# Spectra1.net
KiCad netlist of a schematic drawn in EAGLE
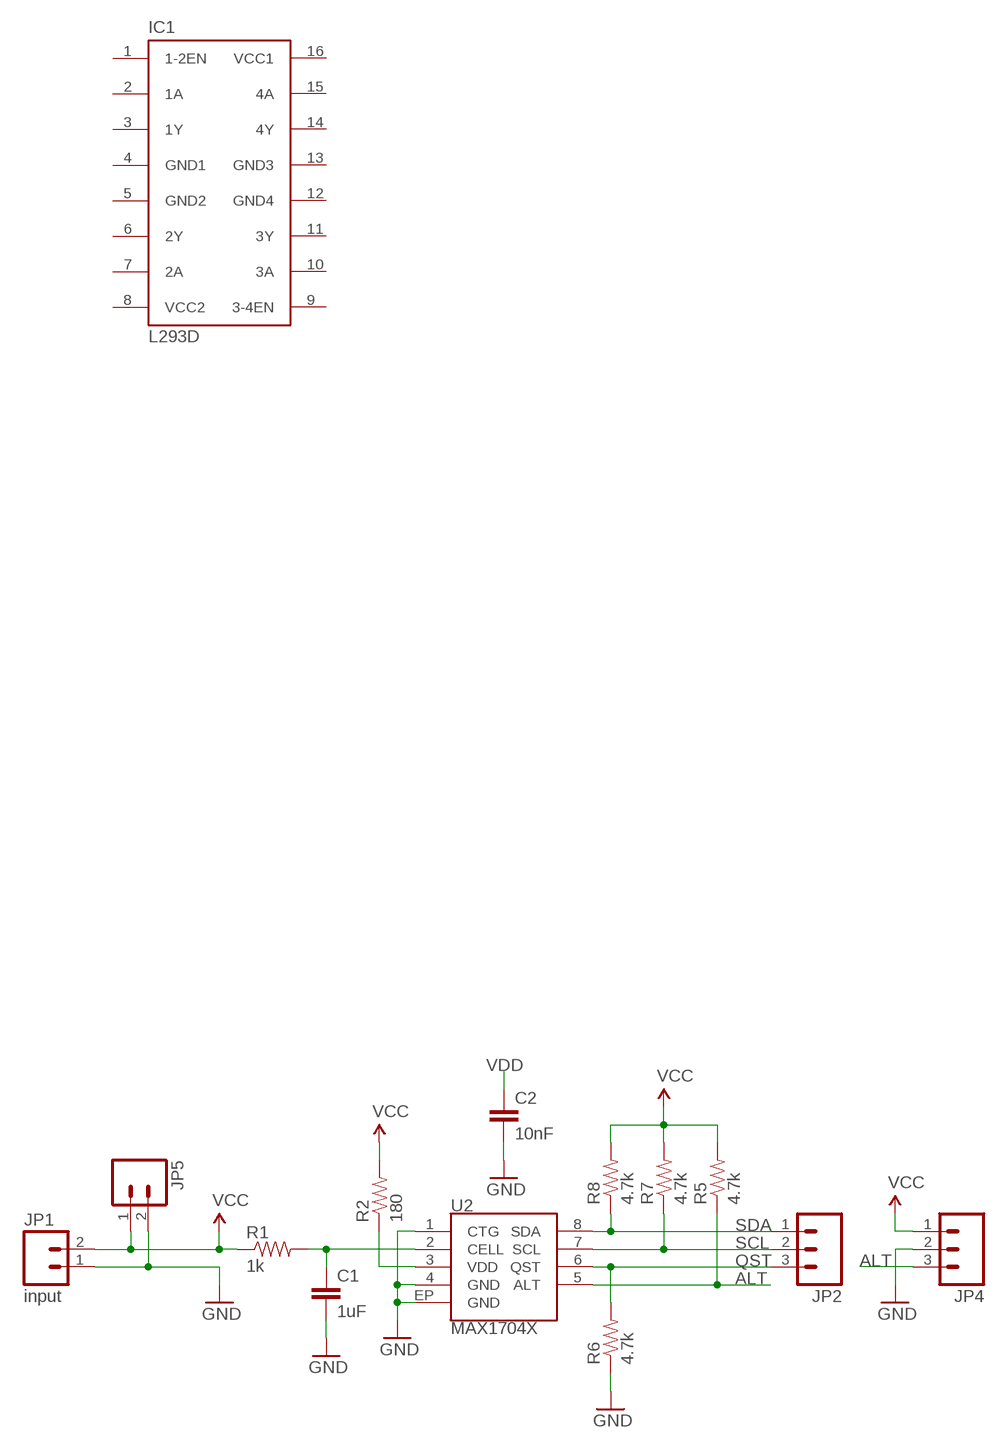
[diagram p0: schematic, sheet 1, part 1 of 2]
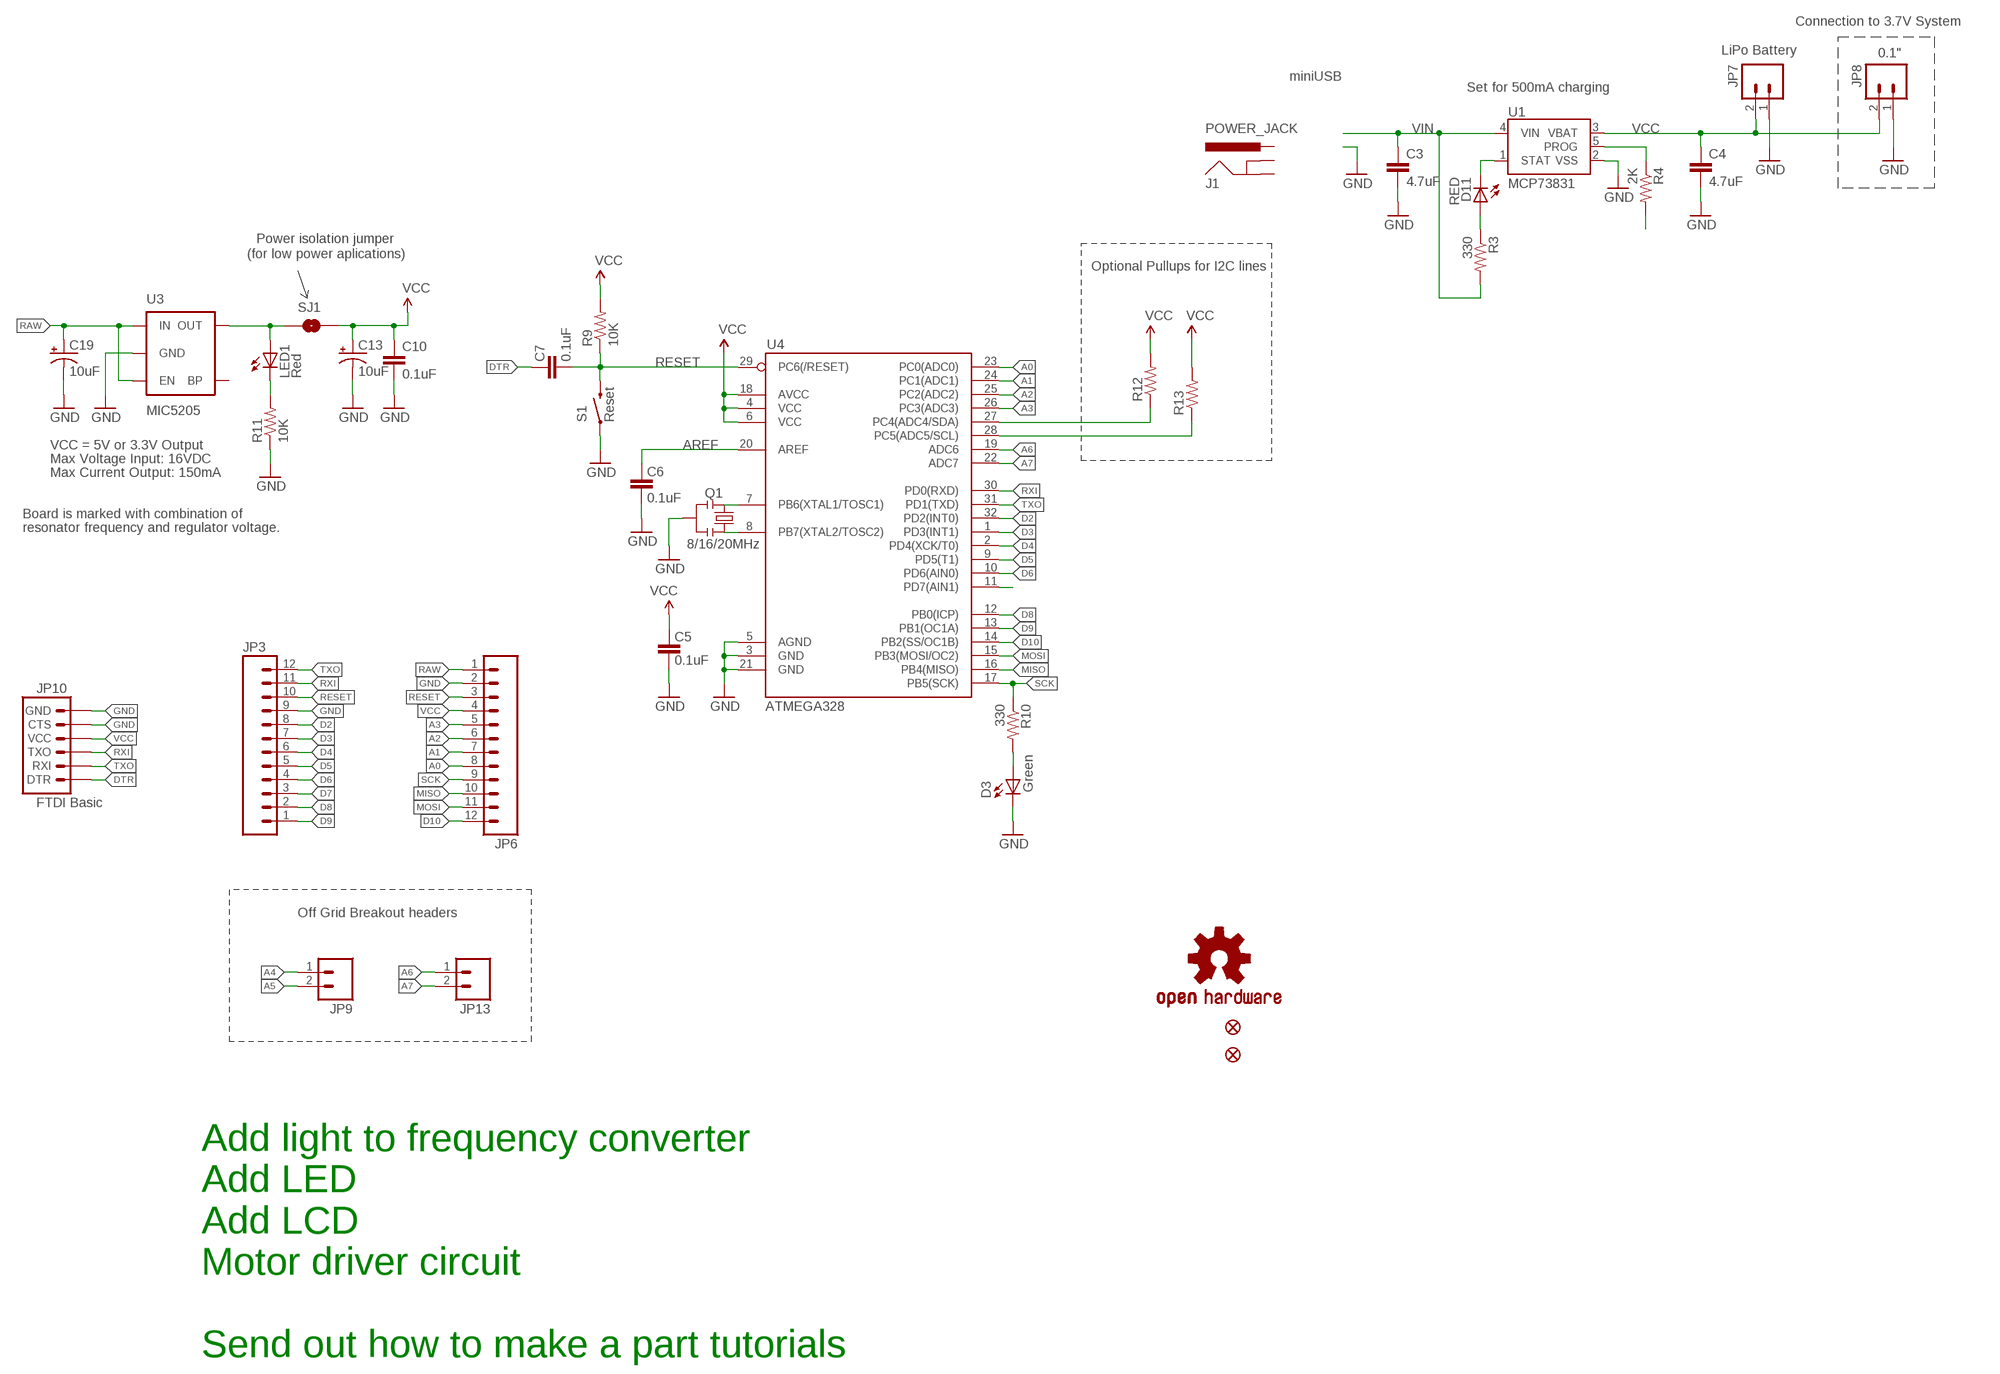
[diagram p1: schematic, sheet 1, part 2 of 2]

(export (version "E")
  (design (tool "Eeschema 10.0.6"))
  (components
    (comp (ref "C1")
      (value "1uF")
      (footprint "eagle-import:0402-CAP")
      (libsource (lib "eagle-import") (part "CAP0402-CAP"))
    )
    (comp (ref "C2")
      (value "10nF")
      (footprint "eagle-import:0402-CAP")
      (libsource (lib "eagle-import") (part "CAP0402-CAP"))
    )
    (comp (ref "C3")
      (value "4.7uF")
      (footprint "eagle-import:0402-CAP")
      (libsource (lib "eagle-import") (part "CAP0402-CAP"))
    )
    (comp (ref "C4")
      (value "4.7uF")
      (footprint "eagle-import:0402-CAP")
      (libsource (lib "eagle-import") (part "CAP0402-CAP"))
    )
    (comp (ref "C5")
      (value "0.1uF")
      (footprint "eagle-import:0603-CAP")
      (libsource (lib "eagle-import") (part "CAP0603-CAP"))
    )
    (comp (ref "C6")
      (value "0.1uF")
      (footprint "eagle-import:0603-CAP")
      (libsource (lib "eagle-import") (part "CAP0603-CAP"))
    )
    (comp (ref "C7")
      (value "0.1uF")
      (footprint "eagle-import:0603-CAP")
      (libsource (lib "eagle-import") (part "CAP0603-CAP"))
    )
    (comp (ref "C10")
      (value "0.1uF")
      (footprint "eagle-import:0603-CAP")
      (libsource (lib "eagle-import") (part "CAP0603-CAP"))
    )
    (comp (ref "C13")
      (value "10uF")
      (footprint "eagle-import:EIA3216")
      (libsource (lib "eagle-import") (part "CAP_POL1206"))
    )
    (comp (ref "C19")
      (value "10uF")
      (footprint "eagle-import:EIA3216")
      (libsource (lib "eagle-import") (part "CAP_POL1206"))
    )
    (comp (ref "D3")
      (value "Green")
      (footprint "eagle-import:0603-LED-ALT1")
      (libsource (lib "eagle-import") (part "LED"))
    )
    (comp (ref "D11")
      (value "RED")
      (footprint "eagle-import:LED-0603")
      (libsource (lib "eagle-import") (part "LED0603"))
    )
    (comp (ref "IC1")
      (value "L293D")
      (footprint "eagle-import:DIL16")
      (libsource (lib "eagle-import") (part "L293D"))
    )
    (comp (ref "J1")
      (value "POWER_JACK")
      (footprint "eagle-import:POWER_JACK_PTH")
      (libsource (lib "eagle-import") (part "POWER_JACK"))
    )
    (comp (ref "JP1")
      (value "input")
      (footprint "eagle-import:JST-2-SMD")
      (libsource (lib "eagle-import") (part "M02-JST-2MM-SMT"))
    )
    (comp (ref "JP2")
      (value "M03PTH")
      (footprint "eagle-import:1X03")
      (libsource (lib "eagle-import") (part "M03PTH"))
    )
    (comp (ref "JP3")
      (value "M12PTH")
      (footprint "eagle-import:1X12")
      (libsource (lib "eagle-import") (part "M12PTH"))
    )
    (comp (ref "JP4")
      (value "M03PTH")
      (footprint "eagle-import:1X03")
      (libsource (lib "eagle-import") (part "M03PTH"))
    )
    (comp (ref "JP5")
      (value "M02PTH")
      (footprint "eagle-import:1X02")
      (libsource (lib "eagle-import") (part "M02PTH"))
    )
    (comp (ref "JP6")
      (value "M12PTH")
      (footprint "eagle-import:1X12")
      (libsource (lib "eagle-import") (part "M12PTH"))
    )
    (comp (ref "JP7")
      (value "LiPo Battery")
      (footprint "eagle-import:JST-2-SMD")
      (libsource (lib "eagle-import") (part "M02-JST-2MM-SMT"))
    )
    (comp (ref "JP8")
      (value "M02PTH")
      (footprint "eagle-import:1X02")
      (libsource (lib "eagle-import") (part "M02PTH"))
    )
    (comp (ref "JP9")
      (value "M02PTH")
      (footprint "eagle-import:1X02")
      (libsource (lib "eagle-import") (part "M02PTH"))
    )
    (comp (ref "JP10")
      (value "FTDI Basic")
      (footprint "eagle-import:1X06")
      (libsource (lib "eagle-import") (part "ARDUINO_SERIAL_PROGRAMPTH"))
    )
    (comp (ref "JP11")
      (value "FIDUCIALUFIDUCIAL")
      (footprint "eagle-import:MICRO-FIDUCIAL")
      (libsource (lib "eagle-import") (part "FIDUCIALUFIDUCIAL"))
    )
    (comp (ref "JP12")
      (value "FIDUCIALUFIDUCIAL")
      (footprint "eagle-import:MICRO-FIDUCIAL")
      (libsource (lib "eagle-import") (part "FIDUCIALUFIDUCIAL"))
    )
    (comp (ref "JP13")
      (value "M02PTH")
      (footprint "eagle-import:1X02")
      (libsource (lib "eagle-import") (part "M02PTH"))
    )
    (comp (ref "LED1")
      (value "Red")
      (footprint "eagle-import:0603-LED-ALT1")
      (libsource (lib "eagle-import") (part "LED"))
    )
    (comp (ref "Q1")
      (value "8/16/20MHz")
      (footprint "eagle-import:RESONATOR-SMD-1_1")
      (libsource (lib "eagle-import") (part "RESONATOR1{colon}1"))
    )
    (comp (ref "R1")
      (value "1k")
      (footprint "eagle-import:0402-RES")
      (libsource (lib "eagle-import") (part "RESISTOR0402-RES"))
    )
    (comp (ref "R2")
      (value "180")
      (footprint "eagle-import:0402-RES")
      (libsource (lib "eagle-import") (part "RESISTOR0402-RES"))
    )
    (comp (ref "R3")
      (value "330")
      (footprint "eagle-import:0402-RES")
      (libsource (lib "eagle-import") (part "RESISTOR0402-RES"))
    )
    (comp (ref "R4")
      (value "2K")
      (footprint "eagle-import:0402-RES")
      (libsource (lib "eagle-import") (part "RESISTOR0402-RES"))
    )
    (comp (ref "R5")
      (value "4.7k")
      (footprint "eagle-import:0402-RES")
      (libsource (lib "eagle-import") (part "RESISTOR0402-RES"))
    )
    (comp (ref "R6")
      (value "4.7k")
      (footprint "eagle-import:0402-RES")
      (libsource (lib "eagle-import") (part "RESISTOR0402-RES"))
    )
    (comp (ref "R7")
      (value "4.7k")
      (footprint "eagle-import:0402-RES")
      (libsource (lib "eagle-import") (part "RESISTOR0402-RES"))
    )
    (comp (ref "R8")
      (value "4.7k")
      (footprint "eagle-import:0402-RES")
      (libsource (lib "eagle-import") (part "RESISTOR0402-RES"))
    )
    (comp (ref "R9")
      (value "10K")
      (footprint "eagle-import:0603-RES")
      (libsource (lib "eagle-import") (part "RESISTOR0603-RES"))
    )
    (comp (ref "R10")
      (value "330")
      (footprint "eagle-import:0603-RES")
      (libsource (lib "eagle-import") (part "RESISTOR0603-RES"))
    )
    (comp (ref "R11")
      (value "10K")
      (footprint "eagle-import:0603-RES")
      (libsource (lib "eagle-import") (part "RESISTOR0603-RES"))
    )
    (comp (ref "R12")
      (value "RESISTOR0603-RES")
      (footprint "eagle-import:0603-RES")
      (libsource (lib "eagle-import") (part "RESISTOR0603-RES"))
    )
    (comp (ref "R13")
      (value "RESISTOR0603-RES")
      (footprint "eagle-import:0603-RES")
      (libsource (lib "eagle-import") (part "RESISTOR0603-RES"))
    )
    (comp (ref "S1")
      (value "Reset")
      (footprint "eagle-import:TACTILE-SWITCH-SMD-ALT01")
      (libsource (lib "eagle-import") (part "SWITCH-MOMENTARY-2SMD-ALT01"))
    )
    (comp (ref "SJ1")
      (value "SOLDERJUMPERNC")
      (footprint "eagle-import:SJ_2S")
      (libsource (lib "eagle-import") (part "SOLDERJUMPERNC"))
    )
    (comp (ref "U$3")
      (value "OSHW-LOGOS")
      (footprint "eagle-import:OSHW-LOGO-S")
      (libsource (lib "eagle-import") (part "OSHW-LOGOS"))
    )
    (comp (ref "U1")
      (value "MCP73831")
      (footprint "eagle-import:SOT23-5")
      (libsource (lib "eagle-import") (part "MCP73831"))
    )
    (comp (ref "U2")
      (value "MAX1704X")
      (footprint "eagle-import:TDFN-8")
      (libsource (lib "eagle-import") (part "MAX1704X"))
    )
    (comp (ref "U3")
      (value "MIC5205")
      (footprint "eagle-import:SOT23-5")
      (libsource (lib "eagle-import") (part "V_REG_LDOSMD"))
    )
    (comp (ref "U4")
      (value "ATMEGA328")
      (footprint "eagle-import:TQFP32-08")
      (libsource (lib "eagle-import") (part "ATMEGA168"))
    )
  )
  (nets
    (net (code "1") (name "/ALT") (class "Default")
      (node (ref "JP4") (pin "3") (pinfunction "3_3") (pintype "passive"))
      (node (ref "R5") (pin "1") (pinfunction "1_1") (pintype "passive"))
      (node (ref "U2") (pin "5") (pinfunction "ALT_5") (pintype "bidirectional"))
    )
    (net (code "2") (name "/AREF") (class "Default")
      (node (ref "C6") (pin "2") (pinfunction "2_2") (pintype "passive"))
      (node (ref "U4") (pin "20") (pinfunction "AREF_20") (pintype "bidirectional"))
    )
    (net (code "3") (name "/CHRG.CTRL") (class "Default")
      (node (ref "R4") (pin "2") (pinfunction "2_2") (pintype "passive"))
      (node (ref "U4") (pin "11") (pinfunction "PD7(AIN1)_11") (pintype "bidirectional"))
    )
    (net (code "4") (name "/GND1") (class "Default")
      (node (ref "IC1") (pin "4") (pinfunction "GND1_4") (pintype "power_in"))
    )
    (net (code "5") (name "/GND2") (class "Default")
      (node (ref "IC1") (pin "5") (pinfunction "GND2_5") (pintype "power_in"))
    )
    (net (code "6") (name "/GND3") (class "Default")
      (node (ref "IC1") (pin "13") (pinfunction "GND3_13") (pintype "power_in"))
    )
    (net (code "7") (name "/GND4") (class "Default")
      (node (ref "IC1") (pin "12") (pinfunction "GND4_12") (pintype "power_in"))
    )
    (net (code "8") (name "/QST") (class "Default")
      (node (ref "JP2") (pin "3") (pinfunction "3_3") (pintype "passive"))
      (node (ref "R6") (pin "2") (pinfunction "2_2") (pintype "passive"))
      (node (ref "U2") (pin "6") (pinfunction "QST_6") (pintype "bidirectional"))
    )
    (net (code "9") (name "/SCL") (class "Default")
      (node (ref "JP2") (pin "2") (pinfunction "2_2") (pintype "passive"))
      (node (ref "R7") (pin "1") (pinfunction "1_1") (pintype "passive"))
      (node (ref "U2") (pin "7") (pinfunction "SCL_7") (pintype "bidirectional"))
    )
    (net (code "10") (name "/SDA") (class "Default")
      (node (ref "JP2") (pin "1") (pinfunction "1_1") (pintype "passive"))
      (node (ref "R8") (pin "1") (pinfunction "1_1") (pintype "passive"))
      (node (ref "U2") (pin "8") (pinfunction "SDA_8") (pintype "bidirectional"))
    )
    (net (code "11") (name "/VCC1") (class "Default")
      (node (ref "IC1") (pin "16") (pinfunction "VCC1_16") (pintype "power_in"))
    )
    (net (code "12") (name "/VCC2") (class "Default")
      (node (ref "IC1") (pin "8") (pinfunction "VCC2_8") (pintype "power_in"))
    )
    (net (code "13") (name "/VDD") (class "Default")
      (node (ref "C2") (pin "1") (pinfunction "1_1") (pintype "passive"))
      (node (ref "R2") (pin "1") (pinfunction "1_1") (pintype "passive"))
      (node (ref "U2") (pin "3") (pinfunction "VDD_3") (pintype "bidirectional"))
    )
    (net (code "14") (name "/VIN") (class "Default")
      (node (ref "C3") (pin "1") (pinfunction "1_1") (pintype "passive"))
      (node (ref "R3") (pin "2") (pinfunction "2_2") (pintype "passive"))
      (node (ref "U1") (pin "4") (pinfunction "VIN_4") (pintype "power_in"))
    )
    (net (code "15") (name "A0") (class "Default")
      (node (ref "JP6") (pin "8") (pinfunction "8_8") (pintype "passive"))
      (node (ref "U4") (pin "23") (pinfunction "PC0(ADC0)_23") (pintype "bidirectional"))
    )
    (net (code "16") (name "A1") (class "Default")
      (node (ref "JP6") (pin "7") (pinfunction "7_7") (pintype "passive"))
      (node (ref "U4") (pin "24") (pinfunction "PC1(ADC1)_24") (pintype "bidirectional"))
    )
    (net (code "17") (name "A2") (class "Default")
      (node (ref "JP6") (pin "6") (pinfunction "6_6") (pintype "passive"))
      (node (ref "U4") (pin "25") (pinfunction "PC2(ADC2)_25") (pintype "bidirectional"))
    )
    (net (code "18") (name "A3") (class "Default")
      (node (ref "JP6") (pin "5") (pinfunction "5_5") (pintype "passive"))
      (node (ref "U4") (pin "26") (pinfunction "PC3(ADC3)_26") (pintype "bidirectional"))
    )
    (net (code "19") (name "A4") (class "Default")
      (node (ref "JP9") (pin "1") (pinfunction "1_1") (pintype "passive"))
      (node (ref "R12") (pin "1") (pinfunction "1_1") (pintype "passive"))
      (node (ref "U4") (pin "27") (pinfunction "PC4(ADC4/SDA)_27") (pintype "bidirectional"))
    )
    (net (code "20") (name "A5") (class "Default")
      (node (ref "JP9") (pin "2") (pinfunction "2_2") (pintype "passive"))
      (node (ref "R13") (pin "1") (pinfunction "1_1") (pintype "passive"))
      (node (ref "U4") (pin "28") (pinfunction "PC5(ADC5/SCL)_28") (pintype "bidirectional"))
    )
    (net (code "21") (name "A6") (class "Default")
      (node (ref "JP13") (pin "1") (pinfunction "1_1") (pintype "passive"))
      (node (ref "U4") (pin "19") (pinfunction "ADC6_19") (pintype "bidirectional"))
    )
    (net (code "22") (name "A7") (class "Default")
      (node (ref "JP13") (pin "2") (pinfunction "2_2") (pintype "passive"))
      (node (ref "U4") (pin "22") (pinfunction "ADC7_22") (pintype "bidirectional"))
    )
    (net (code "23") (name "D2") (class "Default")
      (node (ref "JP3") (pin "8") (pinfunction "8_8") (pintype "passive"))
      (node (ref "U4") (pin "32") (pinfunction "PD2(INT0)_32") (pintype "bidirectional"))
    )
    (net (code "24") (name "D3") (class "Default")
      (node (ref "JP3") (pin "7") (pinfunction "7_7") (pintype "passive"))
      (node (ref "U4") (pin "1") (pinfunction "PD3(INT1)_1") (pintype "bidirectional"))
    )
    (net (code "25") (name "D4") (class "Default")
      (node (ref "JP3") (pin "6") (pinfunction "6_6") (pintype "passive"))
      (node (ref "U4") (pin "2") (pinfunction "PD4(XCK/T0)_2") (pintype "bidirectional"))
    )
    (net (code "26") (name "D5") (class "Default")
      (node (ref "JP3") (pin "5") (pinfunction "5_5") (pintype "passive"))
      (node (ref "U4") (pin "9") (pinfunction "PD5(T1)_9") (pintype "bidirectional"))
    )
    (net (code "27") (name "D6") (class "Default")
      (node (ref "JP3") (pin "4") (pinfunction "4_4") (pintype "passive"))
      (node (ref "U4") (pin "10") (pinfunction "PD6(AIN0)_10") (pintype "bidirectional"))
    )
    (net (code "28") (name "D7") (class "Default")
      (node (ref "JP3") (pin "3") (pinfunction "3_3") (pintype "passive"))
    )
    (net (code "29") (name "D8") (class "Default")
      (node (ref "JP3") (pin "2") (pinfunction "2_2") (pintype "passive"))
      (node (ref "U4") (pin "12") (pinfunction "PB0(ICP)_12") (pintype "bidirectional"))
    )
    (net (code "30") (name "D9") (class "Default")
      (node (ref "JP3") (pin "1") (pinfunction "1_1") (pintype "passive"))
      (node (ref "U4") (pin "13") (pinfunction "PB1(OC1A)_13") (pintype "bidirectional"))
    )
    (net (code "31") (name "D10") (class "Default")
      (node (ref "JP6") (pin "12") (pinfunction "12_12") (pintype "passive"))
      (node (ref "U4") (pin "14") (pinfunction "PB2(SS/OC1B)_14") (pintype "bidirectional"))
    )
    (net (code "32") (name "DTR") (class "Default")
      (node (ref "C7") (pin "2") (pinfunction "2_2") (pintype "passive"))
      (node (ref "JP10") (pin "1") (pinfunction "DTR_1") (pintype "passive"))
    )
    (net (code "33") (name "GND") (class "Default")
      (node (ref "C1") (pin "2") (pinfunction "2_2") (pintype "passive"))
      (node (ref "C10") (pin "2") (pinfunction "2_2") (pintype "passive"))
      (node (ref "C13") (pin "C") (pinfunction "-_C") (pintype "passive"))
      (node (ref "C19") (pin "C") (pinfunction "-_C") (pintype "passive"))
      (node (ref "C2") (pin "2") (pinfunction "2_2") (pintype "passive"))
      (node (ref "C3") (pin "2") (pinfunction "2_2") (pintype "passive"))
      (node (ref "C4") (pin "2") (pinfunction "2_2") (pintype "passive"))
      (node (ref "C5") (pin "1") (pinfunction "1_1") (pintype "passive"))
      (node (ref "C6") (pin "1") (pinfunction "1_1") (pintype "passive"))
      (node (ref "D3") (pin "C") (pinfunction "C_C") (pintype "passive"))
      (node (ref "JP1") (pin "1") (pinfunction "1_1") (pintype "passive"))
      (node (ref "JP10") (pin "5") (pinfunction "CTS_5") (pintype "passive"))
      (node (ref "JP10") (pin "6") (pinfunction "GND_6") (pintype "passive"))
      (node (ref "JP3") (pin "9") (pinfunction "9_9") (pintype "passive"))
      (node (ref "JP4") (pin "2") (pinfunction "2_2") (pintype "passive"))
      (node (ref "JP5") (pin "2") (pinfunction "2_2") (pintype "passive"))
      (node (ref "JP6") (pin "2") (pinfunction "2_2") (pintype "passive"))
      (node (ref "JP7") (pin "1") (pinfunction "1_1") (pintype "passive"))
      (node (ref "JP8") (pin "1") (pinfunction "1_1") (pintype "passive"))
      (node (ref "Q1") (pin "2") (pinfunction "2_2") (pintype "passive"))
      (node (ref "R11") (pin "1") (pinfunction "1_1") (pintype "passive"))
      (node (ref "R6") (pin "1") (pinfunction "1_1") (pintype "passive"))
      (node (ref "S1") (pin "1") (pinfunction "1_1") (pintype "passive"))
      (node (ref "S1") (pin "2") (pinfunction "1_2") (pintype "passive"))
      (node (ref "U1") (pin "2") (pinfunction "VSS_2") (pintype "power_in"))
      (node (ref "U2") (pin "1") (pinfunction "CTG_1") (pintype "bidirectional"))
      (node (ref "U2") (pin "4") (pinfunction "GND_4") (pintype "bidirectional"))
      (node (ref "U2") (pin "EP") (pinfunction "GND_EP") (pintype "bidirectional"))
      (node (ref "U3") (pin "2") (pinfunction "GND_2") (pintype "input"))
      (node (ref "U4") (pin "21") (pinfunction "GND_21") (pintype "bidirectional"))
      (node (ref "U4") (pin "3") (pinfunction "GND_3") (pintype "bidirectional"))
      (node (ref "U4") (pin "5") (pinfunction "AGND_5") (pintype "bidirectional"))
    )
    (net (code "34") (name "MISO") (class "Default")
      (node (ref "JP6") (pin "10") (pinfunction "10_10") (pintype "passive"))
      (node (ref "U4") (pin "16") (pinfunction "PB4(MISO)_16") (pintype "bidirectional"))
    )
    (net (code "35") (name "MOSI") (class "Default")
      (node (ref "JP6") (pin "11") (pinfunction "11_11") (pintype "passive"))
      (node (ref "U4") (pin "15") (pinfunction "PB3(MOSI/OC2)_15") (pintype "bidirectional"))
    )
    (net (code "36") (name "Net-(D3-PadA)") (class "Default")
      (node (ref "D3") (pin "A") (pinfunction "A_A") (pintype "passive"))
      (node (ref "R10") (pin "2") (pinfunction "2_2") (pintype "passive"))
    )
    (net (code "37") (name "Net-(D11-PadA)") (class "Default")
      (node (ref "D11") (pin "A") (pinfunction "A_A") (pintype "passive"))
      (node (ref "R3") (pin "1") (pinfunction "1_1") (pintype "passive"))
    )
    (net (code "38") (name "Net-(LED1-PadC)") (class "Default")
      (node (ref "LED1") (pin "C") (pinfunction "C_C") (pintype "passive"))
      (node (ref "R11") (pin "2") (pinfunction "2_2") (pintype "passive"))
    )
    (net (code "39") (name "Net-(U1-PROG)") (class "Default")
      (node (ref "R4") (pin "1") (pinfunction "1_1") (pintype "passive"))
      (node (ref "U1") (pin "5") (pinfunction "PROG_5") (pintype "input"))
    )
    (net (code "40") (name "Net-(U1-STAT)") (class "Default")
      (node (ref "D11") (pin "C") (pinfunction "C_C") (pintype "passive"))
      (node (ref "U1") (pin "1") (pinfunction "STAT_1") (pintype "output"))
    )
    (net (code "41") (name "Net-(U2-CELL)") (class "Default")
      (node (ref "C1") (pin "1") (pinfunction "1_1") (pintype "passive"))
      (node (ref "R1") (pin "2") (pinfunction "2_2") (pintype "passive"))
      (node (ref "U2") (pin "2") (pinfunction "CELL_2") (pintype "bidirectional"))
    )
    (net (code "42") (name "Net-(U3-OUT)") (class "Default")
      (node (ref "LED1") (pin "A") (pinfunction "A_A") (pintype "passive"))
      (node (ref "SJ1") (pin "1") (pinfunction "1_1") (pintype "passive"))
      (node (ref "U3") (pin "5") (pinfunction "OUT_5") (pintype "passive"))
    )
    (net (code "43") (name "Net-(U4-PB6(XTAL1{slash}TOSC1))") (class "Default")
      (node (ref "Q1") (pin "1") (pinfunction "1_1") (pintype "passive"))
      (node (ref "U4") (pin "7") (pinfunction "PB6(XTAL1/TOSC1)_7") (pintype "bidirectional"))
    )
    (net (code "44") (name "Net-(U4-PB7(XTAL2{slash}TOSC2))") (class "Default")
      (node (ref "Q1") (pin "3") (pinfunction "3_3") (pintype "passive"))
      (node (ref "U4") (pin "8") (pinfunction "PB7(XTAL2/TOSC2)_8") (pintype "bidirectional"))
    )
    (net (code "45") (name "RAW") (class "Default")
      (node (ref "C19") (pin "A") (pinfunction "+_A") (pintype "passive"))
      (node (ref "JP6") (pin "1") (pinfunction "1_1") (pintype "passive"))
      (node (ref "U3") (pin "1") (pinfunction "IN_1") (pintype "input"))
      (node (ref "U3") (pin "3") (pinfunction "EN_3") (pintype "input"))
    )
    (net (code "46") (name "RESET") (class "Default")
      (node (ref "C7") (pin "1") (pinfunction "1_1") (pintype "passive"))
      (node (ref "JP3") (pin "10") (pinfunction "10_10") (pintype "passive"))
      (node (ref "JP6") (pin "3") (pinfunction "3_3") (pintype "passive"))
      (node (ref "R9") (pin "1") (pinfunction "1_1") (pintype "passive"))
      (node (ref "S1") (pin "3") (pinfunction "2_3") (pintype "passive"))
      (node (ref "S1") (pin "4") (pinfunction "2_4") (pintype "passive"))
      (node (ref "U4") (pin "29") (pinfunction "PC6(/RESET)_29") (pintype "bidirectional"))
    )
    (net (code "47") (name "RXI") (class "Default")
      (node (ref "JP10") (pin "3") (pinfunction "TXO_3") (pintype "passive"))
      (node (ref "JP3") (pin "11") (pinfunction "11_11") (pintype "passive"))
      (node (ref "U4") (pin "30") (pinfunction "PD0(RXD)_30") (pintype "bidirectional"))
    )
    (net (code "48") (name "SCK") (class "Default")
      (node (ref "JP6") (pin "9") (pinfunction "9_9") (pintype "passive"))
      (node (ref "R10") (pin "1") (pinfunction "1_1") (pintype "passive"))
      (node (ref "U4") (pin "17") (pinfunction "PB5(SCK)_17") (pintype "bidirectional"))
    )
    (net (code "49") (name "TXO") (class "Default")
      (node (ref "JP10") (pin "2") (pinfunction "RXI_2") (pintype "passive"))
      (node (ref "JP3") (pin "12") (pinfunction "12_12") (pintype "passive"))
      (node (ref "U4") (pin "31") (pinfunction "PD1(TXD)_31") (pintype "bidirectional"))
    )
    (net (code "50") (name "VCC") (class "Default")
      (node (ref "C10") (pin "1") (pinfunction "1_1") (pintype "passive"))
      (node (ref "C13") (pin "A") (pinfunction "+_A") (pintype "passive"))
      (node (ref "C4") (pin "1") (pinfunction "1_1") (pintype "passive"))
      (node (ref "C5") (pin "2") (pinfunction "2_2") (pintype "passive"))
      (node (ref "JP1") (pin "2") (pinfunction "2_2") (pintype "passive"))
      (node (ref "JP10") (pin "4") (pinfunction "VCC_4") (pintype "passive"))
      (node (ref "JP4") (pin "1") (pinfunction "1_1") (pintype "passive"))
      (node (ref "JP5") (pin "1") (pinfunction "1_1") (pintype "passive"))
      (node (ref "JP6") (pin "4") (pinfunction "4_4") (pintype "passive"))
      (node (ref "JP7") (pin "2") (pinfunction "2_2") (pintype "passive"))
      (node (ref "JP8") (pin "2") (pinfunction "2_2") (pintype "passive"))
      (node (ref "R1") (pin "1") (pinfunction "1_1") (pintype "passive"))
      (node (ref "R12") (pin "2") (pinfunction "2_2") (pintype "passive"))
      (node (ref "R13") (pin "2") (pinfunction "2_2") (pintype "passive"))
      (node (ref "R2") (pin "2") (pinfunction "2_2") (pintype "passive"))
      (node (ref "R5") (pin "2") (pinfunction "2_2") (pintype "passive"))
      (node (ref "R7") (pin "2") (pinfunction "2_2") (pintype "passive"))
      (node (ref "R8") (pin "2") (pinfunction "2_2") (pintype "passive"))
      (node (ref "R9") (pin "2") (pinfunction "2_2") (pintype "passive"))
      (node (ref "SJ1") (pin "2") (pinfunction "2_2") (pintype "passive"))
      (node (ref "U1") (pin "3") (pinfunction "VBAT_3") (pintype "power_in"))
      (node (ref "U4") (pin "18") (pinfunction "AVCC_18") (pintype "bidirectional"))
      (node (ref "U4") (pin "4") (pinfunction "VCC_4") (pintype "bidirectional"))
      (node (ref "U4") (pin "6") (pinfunction "VCC_6") (pintype "bidirectional"))
    )
    (net (code "51") (name "unconnected-(IC1-1-2EN-Pad1)") (class "Default")
      (node (ref "IC1") (pin "1") (pinfunction "1-2EN_1") (pintype "input"))
    )
    (net (code "52") (name "unconnected-(IC1-1A-Pad2)") (class "Default")
      (node (ref "IC1") (pin "2") (pinfunction "1A_2") (pintype "input"))
    )
    (net (code "53") (name "unconnected-(IC1-1Y-Pad3)") (class "Default")
      (node (ref "IC1") (pin "3") (pinfunction "1Y_3") (pintype "output"))
    )
    (net (code "54") (name "unconnected-(IC1-2A-Pad7)") (class "Default")
      (node (ref "IC1") (pin "7") (pinfunction "2A_7") (pintype "input"))
    )
    (net (code "55") (name "unconnected-(IC1-2Y-Pad6)") (class "Default")
      (node (ref "IC1") (pin "6") (pinfunction "2Y_6") (pintype "output"))
    )
    (net (code "56") (name "unconnected-(IC1-3-4EN-Pad9)") (class "Default")
      (node (ref "IC1") (pin "9") (pinfunction "3-4EN_9") (pintype "input"))
    )
    (net (code "57") (name "unconnected-(IC1-3A-Pad10)") (class "Default")
      (node (ref "IC1") (pin "10") (pinfunction "3A_10") (pintype "input"))
    )
    (net (code "58") (name "unconnected-(IC1-3Y-Pad11)") (class "Default")
      (node (ref "IC1") (pin "11") (pinfunction "3Y_11") (pintype "output"))
    )
    (net (code "59") (name "unconnected-(IC1-4A-Pad15)") (class "Default")
      (node (ref "IC1") (pin "15") (pinfunction "4A_15") (pintype "input"))
    )
    (net (code "60") (name "unconnected-(IC1-4Y-Pad14)") (class "Default")
      (node (ref "IC1") (pin "14") (pinfunction "4Y_14") (pintype "output"))
    )
    (net (code "61") (name "unconnected-(J1-PadGND)") (class "Default")
      (node (ref "J1") (pin "GND") (pinfunction "GND_GND") (pintype "bidirectional"))
    )
    (net (code "62") (name "unconnected-(J1-PadGNDBREAK)") (class "Default")
      (node (ref "J1") (pin "GNDBREAK") (pinfunction "GNDBREAK_GNDBREAK") (pintype "bidirectional"))
    )
    (net (code "63") (name "unconnected-(J1-PadPWR)") (class "Default")
      (node (ref "J1") (pin "PWR") (pinfunction "PWR_PWR") (pintype "bidirectional"))
    )
    (net (code "64") (name "unconnected-(U3-BP-Pad4)") (class "Default")
      (node (ref "U3") (pin "4") (pinfunction "BP_4") (pintype "input"))
    )
  )
)
